# Schematic.net
KiCad netlist of a schematic drawn in Altium Designer
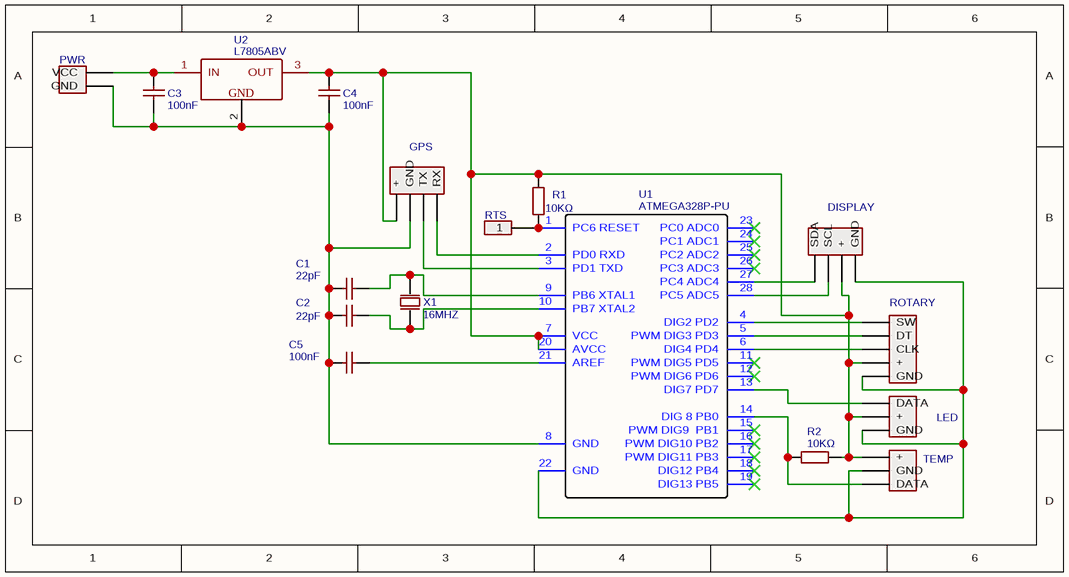
[diagram p0: Schematic.schdoc]

(export (version "E")
  (design (tool "Eeschema 10.0.6"))
  (components
    (comp (ref "C1")
      (value "22pF")
      (fields
        (field (name "VOLTAGE") "50V")
        (field (name "TOLERANCE") "±10%")
        (field (name "BOM_MANUFACTURER PART") "22pf/50V 10%")
      )
      (libsource (lib "") (part "root_0___4"))
    )
    (comp (ref "C2")
      (value "22pF")
      (fields
        (field (name "VOLTAGE") "50V")
        (field (name "TOLERANCE") "±10%")
        (field (name "BOM_MANUFACTURER PART") "22pf/50V 10%")
      )
      (libsource (lib "") (part "root_0___4"))
    )
    (comp (ref "C3")
      (value "100nF")
      (fields (field (name "TOLERANCE") "20%") (field (name "BOM_MANUFACTURER PART") "CT4-0805Y104M500"))
      (libsource (lib "altium-import") (part "root_1__"))
    )
    (comp (ref "C4")
      (value "100nF")
      (fields (field (name "TOLERANCE") "20%") (field (name "BOM_MANUFACTURER PART") "CT4-0805Y104M500"))
      (libsource (lib "altium-import") (part "root_1__"))
    )
    (comp (ref "C5")
      (value "100nF")
      (fields (field (name "TOLERANCE") "20%") (field (name "BOM_MANUFACTURER PART") "CT4-0805Y104M500"))
      (libsource (lib "") (part "root_2___2"))
    )
    (comp (ref "DISPLAY")
      (value "Header-Male-2.54_1x4")
      (fields (field (name "BOM_MANUFACTURER PART") "Headers??Pins 1*4P"))
      (libsource (lib "") (part "root_1___1"))
    )
    (comp (ref "GPS")
      (value "Header-Male-2.54_1x4")
      (fields (field (name "BOM_MANUFACTURER PART") "Headers??Pins 1*4P"))
      (libsource (lib "") (part "root_1___2"))
    )
    (comp (ref "LED")
      (value "Header-Male-2.54_1x3")
      (fields (field (name "BOM_MANUFACTURER PART") "Header2.54mm 1*3P"))
      (libsource (lib "altium-import") (part "root_0__"))
    )
    (comp (ref "PWR")
      (value "Header-Male-2.54_1x2")
      (fields (field (name "BOM_MANUFACTURER PART") "2.54mm 1*2P"))
      (libsource (lib "") (part "root_2___1"))
    )
    (comp (ref "R1")
      (value "10KΩ")
      (fields
        (field (name "POWER") "1/4W")
        (field (name "TOLERANCE") "±1%")
        (field (name "BOM_MANUFACTURER PART") "MFR0W4F1002A50")
      )
      (libsource (lib "altium-import") (part "root_3__"))
    )
    (comp (ref "R2")
      (value "10KΩ")
      (fields
        (field (name "POWER") "1/4W")
        (field (name "TOLERANCE") "±1%")
        (field (name "BOM_MANUFACTURER PART") "MFR0W4F1002A50")
      )
      (libsource (lib "") (part "root_0___5"))
    )
    (comp (ref "ROTARY")
      (value "Header-Male-2.54_1x5")
      (fields (field (name "BOM_MANUFACTURER PART") "2.54mm 1*5P Header"))
      (libsource (lib "") (part "root_0___1"))
    )
    (comp (ref "RTS")
      (value "Header-Male-2.54_1x1")
      (fields (field (name "BOM_MANUFACTURER PART") "Header 1*1P"))
      (libsource (lib "altium-import") (part "root_2__"))
    )
    (comp (ref "TEMP")
      (value "Header-Male-2.54_1x3")
      (fields (field (name "BOM_MANUFACTURER PART") "Header2.54mm 1*3P"))
      (libsource (lib "") (part "root_0___6"))
    )
    (comp (ref "U1") (value "ATMEGA328P-PU") (libsource (lib "") (part "root_0___3")))
    (comp (ref "U2") (value "L7805ABV") (libsource (lib "") (part "root_0___2")))
    (comp (ref "X1")
      (value "16MHZ")
      (fields (field (name "BOM_MANUFACTURER PART") "X49SD16MSD2SC"))
      (libsource (lib "") (part "root_3___1"))
    )
  )
  (nets
    (net (code "1") (name "Net-(DISPLAY-+)") (class "Default")
      (node (ref "C4") (pin "2") (pinfunction "2_2") (pintype "passive"))
      (node (ref "DISPLAY") (pin "3") (pinfunction "+_3") (pintype "passive"))
      (node (ref "GPS") (pin "1") (pinfunction "+_1") (pintype "passive"))
      (node (ref "LED") (pin "2") (pinfunction "+_2") (pintype "passive"))
      (node (ref "R1") (pin "1") (pinfunction "1_1") (pintype "passive"))
      (node (ref "R2") (pin "2") (pinfunction "2_2") (pintype "passive"))
      (node (ref "ROTARY") (pin "4") (pinfunction "+_4") (pintype "passive"))
      (node (ref "TEMP") (pin "1") (pinfunction "+_1") (pintype "passive"))
      (node (ref "U1") (pin "20") (pinfunction "AVCC_20") (pintype "passive"))
      (node (ref "U1") (pin "7") (pinfunction "VCC_7") (pintype "passive"))
      (node (ref "U2") (pin "3") (pinfunction "OUT_3") (pintype "passive"))
    )
    (net (code "2") (name "Net-(DISPLAY-GND)") (class "Default")
      (node (ref "DISPLAY") (pin "4") (pinfunction "GND_4") (pintype "passive"))
      (node (ref "LED") (pin "3") (pinfunction "GND_3") (pintype "passive"))
      (node (ref "ROTARY") (pin "5") (pinfunction "GND_5") (pintype "passive"))
      (node (ref "TEMP") (pin "2") (pinfunction "GND_2") (pintype "passive"))
      (node (ref "U1") (pin "22") (pinfunction "GND_22") (pintype "passive"))
    )
    (net (code "3") (name "Net-(DISPLAY-SCL)") (class "Default")
      (node (ref "DISPLAY") (pin "2") (pinfunction "SCL_2") (pintype "passive"))
      (node (ref "U1") (pin "28") (pinfunction "PC5_ADC5_28") (pintype "passive"))
    )
    (net (code "4") (name "Net-(DISPLAY-SDA)") (class "Default")
      (node (ref "DISPLAY") (pin "1") (pinfunction "SDA_1") (pintype "passive"))
      (node (ref "U1") (pin "27") (pinfunction "PC4_ADC4_27") (pintype "passive"))
    )
    (net (code "5") (name "Net-(GPS-GND)") (class "Default")
      (node (ref "C1") (pin "1") (pinfunction "1_1") (pintype "passive"))
      (node (ref "C2") (pin "1") (pinfunction "1_1") (pintype "passive"))
      (node (ref "C3") (pin "1") (pinfunction "1_1") (pintype "passive"))
      (node (ref "C4") (pin "1") (pinfunction "1_1") (pintype "passive"))
      (node (ref "C5") (pin "2") (pinfunction "2_2") (pintype "passive"))
      (node (ref "GPS") (pin "2") (pinfunction "GND_2") (pintype "passive"))
      (node (ref "PWR") (pin "1") (pinfunction "GND_1") (pintype "passive"))
      (node (ref "U1") (pin "8") (pinfunction "GND_8") (pintype "passive"))
      (node (ref "U2") (pin "2") (pinfunction "GND_2") (pintype "passive"))
    )
    (net (code "6") (name "Net-(GPS-RX)") (class "Default")
      (node (ref "GPS") (pin "4") (pinfunction "RX_4") (pintype "passive"))
      (node (ref "U1") (pin "2") (pinfunction "PD0_RXD_2") (pintype "passive"))
    )
    (net (code "7") (name "Net-(GPS-TX)") (class "Default")
      (node (ref "GPS") (pin "3") (pinfunction "TX_3") (pintype "passive"))
      (node (ref "U1") (pin "3") (pinfunction "PD1_TXD_3") (pintype "passive"))
    )
    (net (code "8") (name "Net-(LED-DATA)") (class "Default")
      (node (ref "LED") (pin "1") (pinfunction "DATA_1") (pintype "passive"))
      (node (ref "U1") (pin "13") (pinfunction "DIG7_PD7_13") (pintype "passive"))
    )
    (net (code "9") (name "Net-(PWR-VCC)") (class "Default")
      (node (ref "C3") (pin "2") (pinfunction "2_2") (pintype "passive"))
      (node (ref "PWR") (pin "2") (pinfunction "VCC_2") (pintype "passive"))
      (node (ref "U2") (pin "1") (pinfunction "IN_1") (pintype "passive"))
    )
    (net (code "10") (name "Net-(ROTARY-CLK)") (class "Default")
      (node (ref "ROTARY") (pin "3") (pinfunction "CLK_3") (pintype "passive"))
      (node (ref "U1") (pin "6") (pinfunction "DIG4_PD4_6") (pintype "passive"))
    )
    (net (code "11") (name "Net-(ROTARY-DT)") (class "Default")
      (node (ref "ROTARY") (pin "2") (pinfunction "DT_2") (pintype "passive"))
      (node (ref "U1") (pin "5") (pinfunction "PWM_DIG3_PD3_5") (pintype "passive"))
    )
    (net (code "12") (name "Net-(ROTARY-SW)") (class "Default")
      (node (ref "ROTARY") (pin "1") (pinfunction "SW_1") (pintype "passive"))
      (node (ref "U1") (pin "4") (pinfunction "DIG2_PD2_4") (pintype "passive"))
    )
    (net (code "13") (name "Net-(TEMP-DATA)") (class "Default")
      (node (ref "R2") (pin "1") (pinfunction "1_1") (pintype "passive"))
      (node (ref "TEMP") (pin "3") (pinfunction "DATA_3") (pintype "passive"))
      (node (ref "U1") (pin "14") (pinfunction "DIG_8_PB0_14") (pintype "passive"))
    )
    (net (code "14") (name "Net-(U1-AREF)") (class "Default")
      (node (ref "C5") (pin "1") (pinfunction "1_1") (pintype "passive"))
      (node (ref "U1") (pin "21") (pinfunction "AREF_21") (pintype "passive"))
    )
    (net (code "15") (name "Net-(U1-PB6_XTAL1)") (class "Default")
      (node (ref "C1") (pin "2") (pinfunction "2_2") (pintype "passive"))
      (node (ref "U1") (pin "9") (pinfunction "PB6_XTAL1_9") (pintype "passive"))
      (node (ref "X1") (pin "2") (pinfunction "OSC2_2") (pintype "passive"))
    )
    (net (code "16") (name "Net-(U1-PB7_XTAL2)") (class "Default")
      (node (ref "C2") (pin "2") (pinfunction "2_2") (pintype "passive"))
      (node (ref "U1") (pin "10") (pinfunction "PB7_XTAL2_10") (pintype "passive"))
      (node (ref "X1") (pin "1") (pinfunction "OSC1_1") (pintype "passive"))
    )
    (net (code "17") (name "Net-(U1-PC6_RESET)") (class "Default")
      (node (ref "R1") (pin "2") (pinfunction "2_2") (pintype "passive"))
      (node (ref "RTS") (pin "1") (pinfunction "1_1") (pintype "passive"))
      (node (ref "U1") (pin "1") (pinfunction "PC6_RESET_1") (pintype "passive"))
    )
    (net (code "18") (name "unconnected-(U1-DIG12_PB4-Pad18)") (class "Default")
      (node (ref "U1") (pin "18") (pinfunction "DIG12_PB4_18") (pintype "passive+no_connect"))
    )
    (net (code "19") (name "unconnected-(U1-DIG13_PB5-Pad19)") (class "Default")
      (node (ref "U1") (pin "19") (pinfunction "DIG13_PB5_19") (pintype "passive+no_connect"))
    )
    (net (code "20") (name "unconnected-(U1-PC0_ADC0-Pad23)") (class "Default")
      (node (ref "U1") (pin "23") (pinfunction "PC0_ADC0_23") (pintype "passive+no_connect"))
    )
    (net (code "21") (name "unconnected-(U1-PC1_ADC1-Pad24)") (class "Default")
      (node (ref "U1") (pin "24") (pinfunction "PC1_ADC1_24") (pintype "passive+no_connect"))
    )
    (net (code "22") (name "unconnected-(U1-PC2_ADC2-Pad25)") (class "Default")
      (node (ref "U1") (pin "25") (pinfunction "PC2_ADC2_25") (pintype "passive+no_connect"))
    )
    (net (code "23") (name "unconnected-(U1-PC3_ADC3-Pad26)") (class "Default")
      (node (ref "U1") (pin "26") (pinfunction "PC3_ADC3_26") (pintype "passive+no_connect"))
    )
    (net (code "24") (name "unconnected-(U1-PWM_DIG5_PD5-Pad11)") (class "Default")
      (node (ref "U1") (pin "11") (pinfunction "PWM_DIG5_PD5_11") (pintype "passive+no_connect"))
    )
    (net (code "25") (name "unconnected-(U1-PWM_DIG6_PD6-Pad12)") (class "Default")
      (node (ref "U1") (pin "12") (pinfunction "PWM_DIG6_PD6_12") (pintype "passive+no_connect"))
    )
    (net (code "26") (name "unconnected-(U1-PWM_DIG9__PB1-Pad15)") (class "Default")
      (node (ref "U1") (pin "15") (pinfunction "PWM_DIG9__PB1_15") (pintype "passive+no_connect"))
    )
    (net (code "27") (name "unconnected-(U1-PWM_DIG10_PB2-Pad16)") (class "Default")
      (node (ref "U1") (pin "16") (pinfunction "PWM_DIG10_PB2_16") (pintype "passive+no_connect"))
    )
    (net (code "28") (name "unconnected-(U1-PWM_DIG11_PB3-Pad17)") (class "Default")
      (node (ref "U1") (pin "17") (pinfunction "PWM_DIG11_PB3_17") (pintype "passive+no_connect"))
    )
  )
)
